# ESP32_Board.net
KiCad netlist of a schematic drawn in EasyEDA Pro
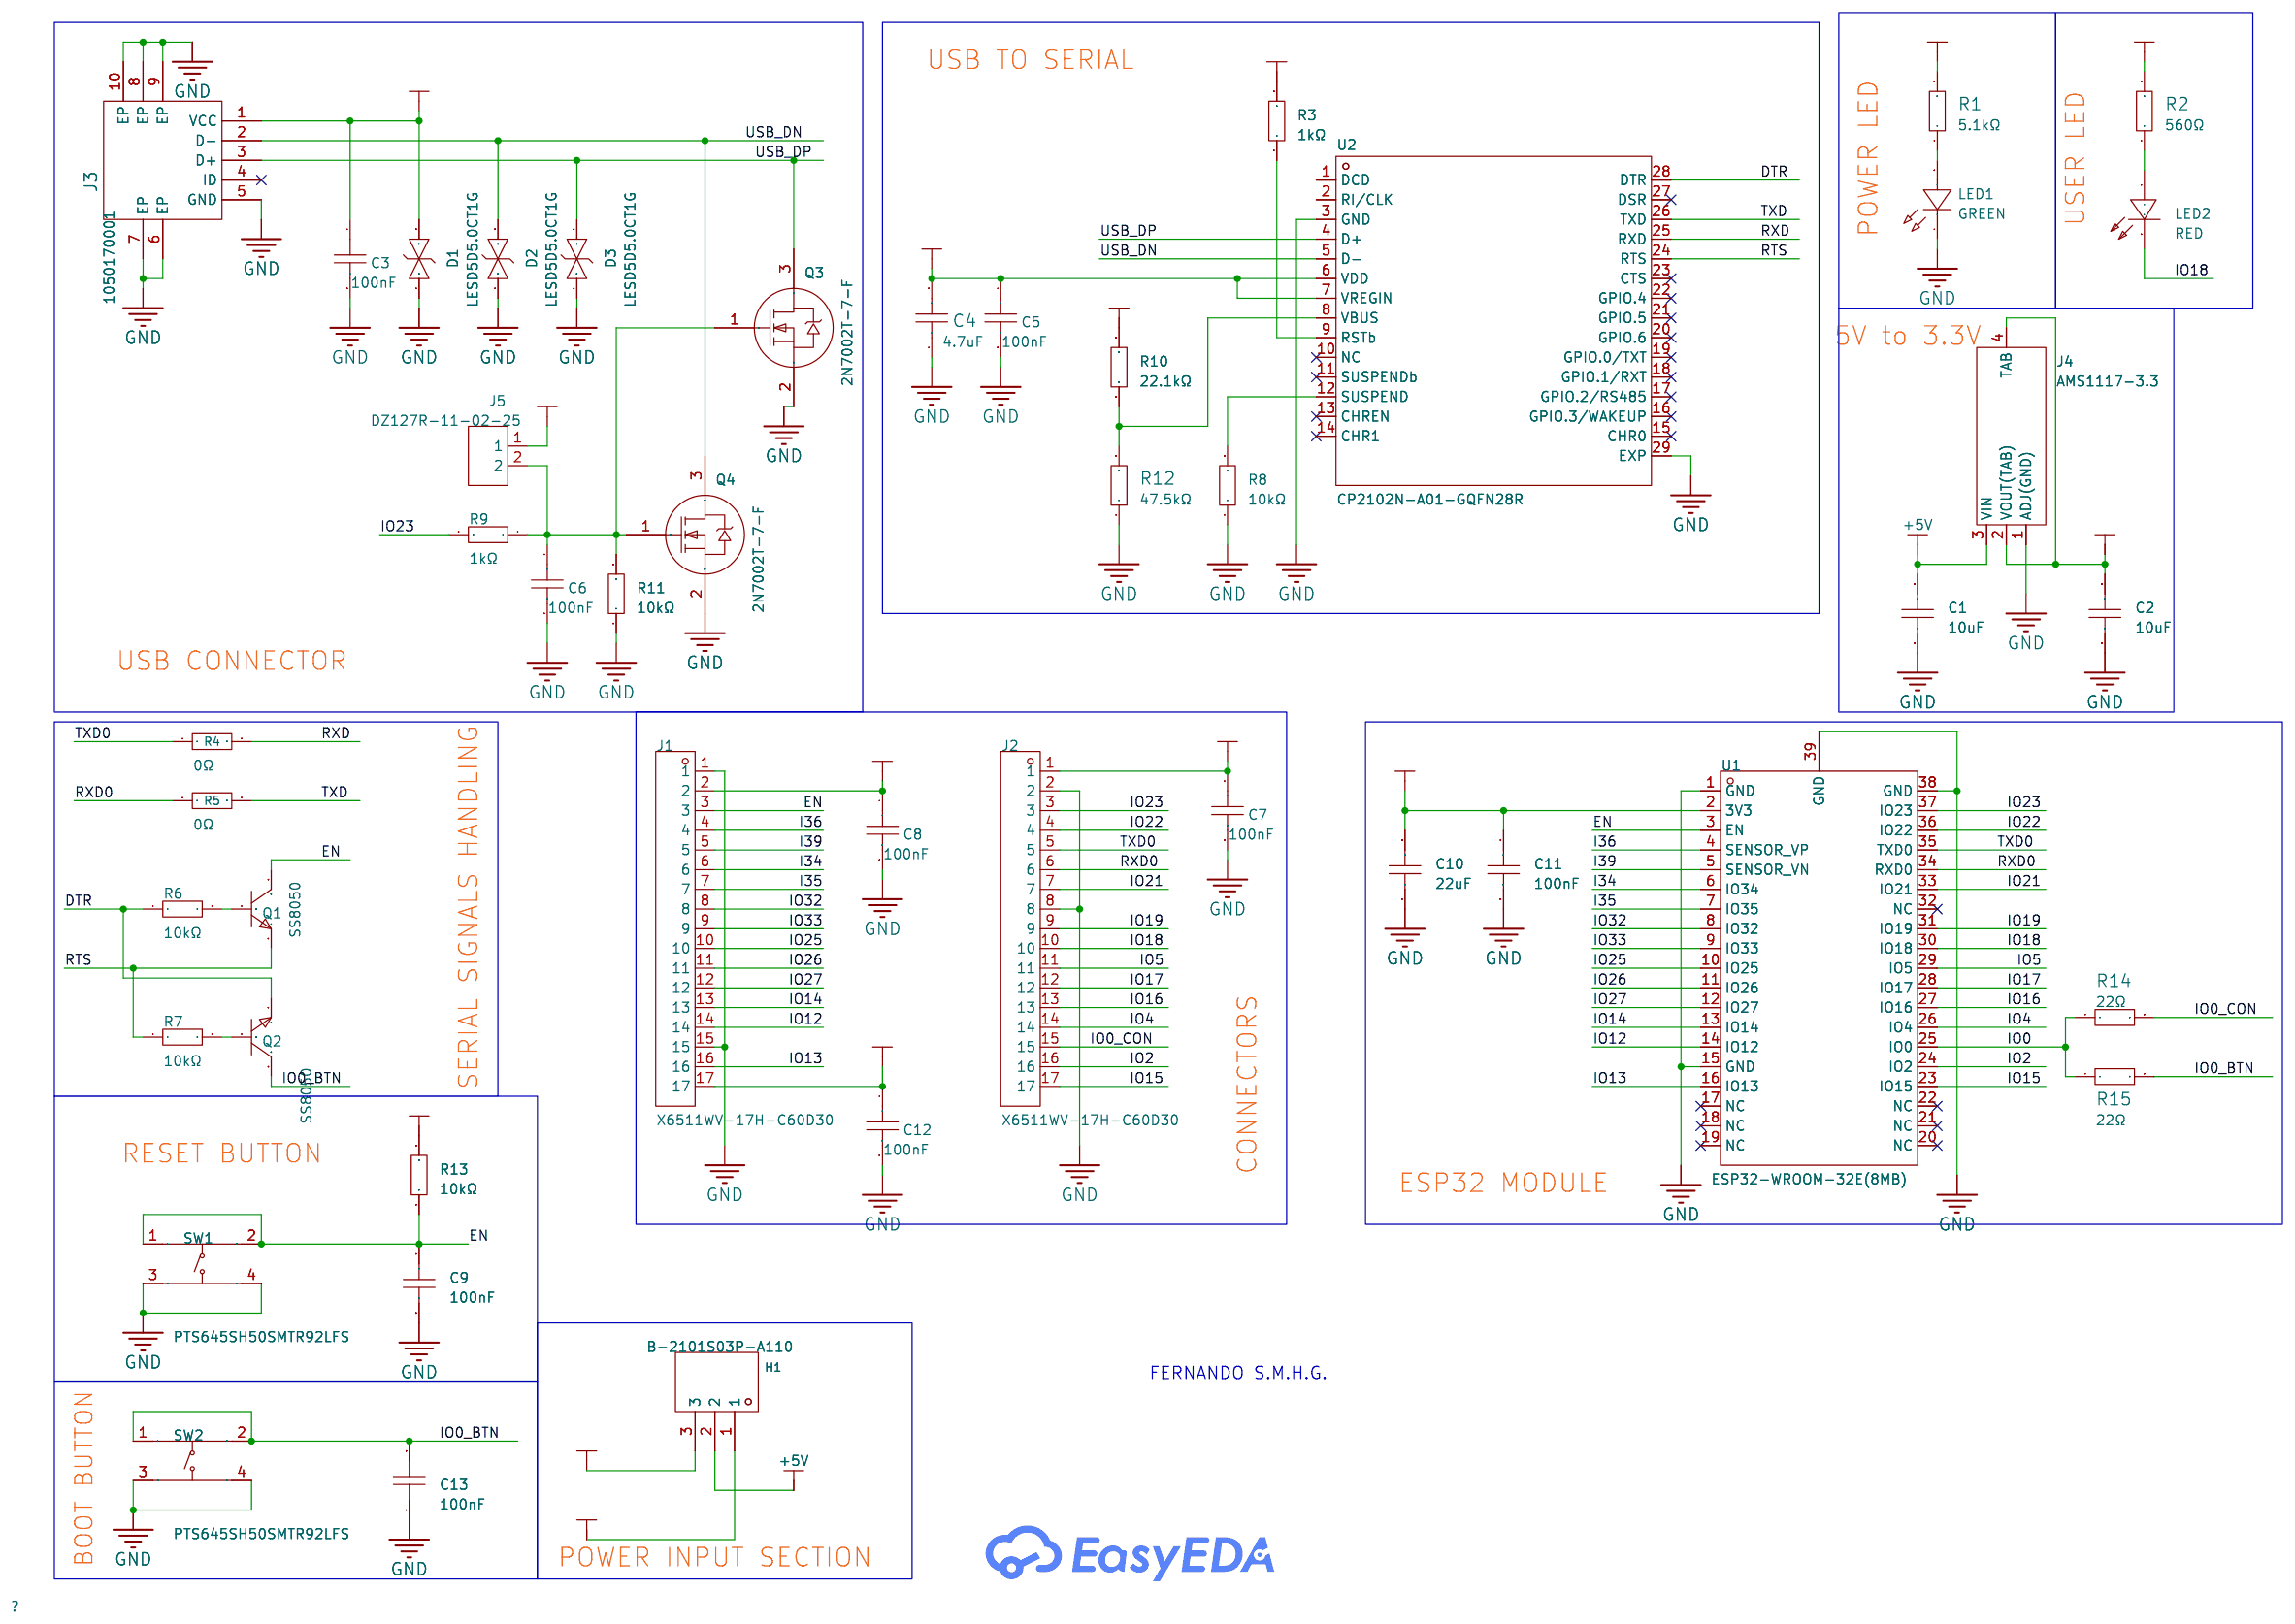
[diagram p0: schematic sheet]

(export (version "E")
  (design (tool "Eeschema 10.0.6"))
  (components
    (comp (ref "C1")
      (value "10uF")
      (footprint "easyedapro:C0402")
      (description "Capacitance:10uF Tolerance:±20% Tolerance:±20% Voltage Rating:10V Temperature Coefficient:X5R")
      (fields
        (field (name "Manufacturer Part") "CL05A106MP5NUNC")
        (field (name "Manufacturer") "SAMSUNG(三星)")
      )
      (libsource (lib "easyedapro") (part "CL05A106MP5NUNC_C315248"))
    )
    (comp (ref "C2")
      (value "10uF")
      (footprint "easyedapro:C0402")
      (description "Capacitance:10uF Tolerance:±20% Tolerance:±20% Voltage Rating:10V Temperature Coefficient:X5R")
      (fields
        (field (name "Manufacturer Part") "CL05A106MP5NUNC")
        (field (name "Manufacturer") "SAMSUNG(三星)")
      )
      (libsource (lib "easyedapro") (part "CL05A106MP5NUNC_C315248"))
    )
    (comp (ref "C3")
      (value "100nF")
      (footprint "easyedapro:C0402")
      (description "Capacitance:100nF Tolerance:±10% Tolerance:±10% Voltage Rating:16V Temperature Coefficient:X7R")
      (fields
        (field (name "Manufacturer Part") "CL05B104KO5NNNC")
        (field (name "Manufacturer") "SAMSUNG(三星)")
      )
      (libsource (lib "easyedapro") (part "CL05B104KO5NNNC"))
    )
    (comp (ref "C4")
      (value "4.7uF")
      (footprint "easyedapro:C0402")
      (description "Capacitance:4.7uF Tolerance:±10% Tolerance:±10% Voltage Rating:10V Temperature Coefficient:X5R")
      (fields
        (field (name "Manufacturer Part") "CL05A475KP5NRNC")
        (field (name "Manufacturer") "SAMSUNG(三星)")
      )
      (libsource (lib "easyedapro") (part "CL05A475KP5NRNC"))
    )
    (comp (ref "C5")
      (value "100nF")
      (footprint "easyedapro:C0402")
      (description "Capacitance:100nF Tolerance:±10% Tolerance:±10% Voltage Rating:16V Temperature Coefficient:X7R")
      (fields
        (field (name "Manufacturer Part") "CL05B104KO5NNNC")
        (field (name "Manufacturer") "SAMSUNG(三星)")
      )
      (libsource (lib "easyedapro") (part "CL05B104KO5NNNC"))
    )
    (comp (ref "C6")
      (value "100nF")
      (footprint "easyedapro:C0402")
      (description "Capacitance:100nF Tolerance:±10% Tolerance:±10% Voltage Rating:16V Temperature Coefficient:X7R")
      (fields
        (field (name "Manufacturer Part") "CL05B104KO5NNNC")
        (field (name "Manufacturer") "SAMSUNG(三星)")
      )
      (libsource (lib "easyedapro") (part "CL05B104KO5NNNC"))
    )
    (comp (ref "C7")
      (value "100nF")
      (footprint "easyedapro:C0402")
      (description "Capacitance:100nF Tolerance:±10% Tolerance:±10% Voltage Rating:16V Temperature Coefficient:X7R")
      (fields
        (field (name "Manufacturer Part") "CL05B104KO5NNNC")
        (field (name "Manufacturer") "SAMSUNG(三星)")
      )
      (libsource (lib "easyedapro") (part "CL05B104KO5NNNC"))
    )
    (comp (ref "C8")
      (value "100nF")
      (footprint "easyedapro:C0402")
      (description "Capacitance:100nF Tolerance:±10% Tolerance:±10% Voltage Rating:16V Temperature Coefficient:X7R")
      (fields
        (field (name "Manufacturer Part") "CL05B104KO5NNNC")
        (field (name "Manufacturer") "SAMSUNG(三星)")
      )
      (libsource (lib "easyedapro") (part "CL05B104KO5NNNC"))
    )
    (comp (ref "C9")
      (value "100nF")
      (footprint "easyedapro:C0402")
      (description "Capacitance:100nF Tolerance:±10% Tolerance:±10% Voltage Rating:16V Temperature Coefficient:X7R")
      (fields
        (field (name "Manufacturer Part") "CL05B104KO5NNNC")
        (field (name "Manufacturer") "SAMSUNG(三星)")
      )
      (libsource (lib "easyedapro") (part "CL05B104KO5NNNC"))
    )
    (comp (ref "C10")
      (value "22uF")
      (footprint "easyedapro:C0805")
      (description "Capacitance:22uF Tolerance:±20% Tolerance:±20% Voltage Rating:25V Temperature Coefficient:X5R")
      (fields
        (field (name "Manufacturer Part") "CL21A226MAYNNNE")
        (field (name "Manufacturer") "SAMSUNG(三星)")
      )
      (libsource (lib "easyedapro") (part "CL21A226MAYNNNE"))
    )
    (comp (ref "C11")
      (value "100nF")
      (footprint "easyedapro:C0402")
      (description "Capacitance:100nF Tolerance:±10% Tolerance:±10% Voltage Rating:16V Temperature Coefficient:X7R")
      (fields
        (field (name "Manufacturer Part") "CL05B104KO5NNNC")
        (field (name "Manufacturer") "SAMSUNG(三星)")
      )
      (libsource (lib "easyedapro") (part "CL05B104KO5NNNC"))
    )
    (comp (ref "C12")
      (value "100nF")
      (footprint "easyedapro:C0402")
      (description "Capacitance:100nF Tolerance:±10% Tolerance:±10% Voltage Rating:16V Temperature Coefficient:X7R")
      (fields
        (field (name "Manufacturer Part") "CL05B104KO5NNNC")
        (field (name "Manufacturer") "SAMSUNG(三星)")
      )
      (libsource (lib "easyedapro") (part "CL05B104KO5NNNC"))
    )
    (comp (ref "C13")
      (value "100nF")
      (footprint "easyedapro:C0402")
      (description "Capacitance:100nF Tolerance:±10% Tolerance:±10% Voltage Rating:16V Temperature Coefficient:X7R")
      (fields
        (field (name "Manufacturer Part") "CL05B104KO5NNNC")
        (field (name "Manufacturer") "SAMSUNG(三星)")
      )
      (libsource (lib "easyedapro") (part "CL05B104KO5NNNC"))
    )
    (comp (ref "D1")
      (value "LESD5D5.0CT1G")
      (footprint "easyedapro:SOD-523_L1.2-W0.8-LS1.6-BI")
      (fields (field (name "Manufacturer") "KUU"))
      (libsource (lib "easyedapro") (part "LESD5D5.0CT1G_C7433850"))
    )
    (comp (ref "D2")
      (value "LESD5D5.0CT1G")
      (footprint "easyedapro:SOD-523_L1.2-W0.8-LS1.6-BI")
      (fields (field (name "Manufacturer") "KUU"))
      (libsource (lib "easyedapro") (part "LESD5D5.0CT1G_C7433850"))
    )
    (comp (ref "D3")
      (value "LESD5D5.0CT1G")
      (footprint "easyedapro:SOD-523_L1.2-W0.8-LS1.6-BI")
      (fields (field (name "Manufacturer") "KUU"))
      (libsource (lib "easyedapro") (part "LESD5D5.0CT1G_C7433850"))
    )
    (comp (ref "H1")
      (value "B-2101S03P-A110")
      (footprint "easyedapro:HDR-TH_3P-P1.27-V-M-1")
      (fields (field (name "Manufacturer") "Ckmtw(灿科盟)"))
      (libsource (lib "easyedapro") (part "210-1S-1*3Ppin Gold-plated"))
    )
    (comp (ref "J1")
      (value "X6511WV-17H-C60D30")
      (footprint "easyedapro:HDR-TH_17P-P2.54-V-M")
      (fields (field (name "Manufacturer") "XKB Connection(中国星坤)"))
      (libsource (lib "easyedapro") (part "X6511WV-17H-C30D60"))
    )
    (comp (ref "J2")
      (value "X6511WV-17H-C60D30")
      (footprint "easyedapro:HDR-TH_17P-P2.54-V-M")
      (fields (field (name "Manufacturer") "XKB Connection(中国星坤)"))
      (libsource (lib "easyedapro") (part "X6511WV-17H-C30D60"))
    )
    (comp (ref "J3")
      (value "1050170001")
      (footprint "easyedapro:MICRO-USB-SMD_105017-0001")
      (fields (field (name "Manufacturer") "MOLEX"))
      (libsource (lib "easyedapro") (part "105017-0001"))
    )
    (comp (ref "J4")
      (value "AMS1117-3.3")
      (footprint "easyedapro:SOT-223-4_L6.5-W3.5-P2.30-LS7.0-BR")
      (fields (field (name "Manufacturer") "UMW(友台半导体)"))
      (libsource (lib "easyedapro") (part "AMS1117-3.3_C347222"))
    )
    (comp (ref "J5")
      (value "DZ127R-11-02-25")
      (footprint "easyedapro:HDR-TH_2P-P1.27-V-M")
      (fields (field (name "Manufacturer") "DEALON(德艺隆)"))
      (libsource (lib "easyedapro") (part "DZ127R-11-02-25"))
    )
    (comp (ref "LED1")
      (value "GREEN")
      (footprint "easyedapro:LED0805-RD")
      (fields (field (name "Manufacturer") "Chau Light(洲光源)"))
      (libsource (lib "easyedapro") (part "ZGH-Z2012C-10L-Z3"))
    )
    (comp (ref "LED2")
      (value "RED")
      (footprint "easyedapro:LED0805-R-RD")
      (fields (field (name "Manufacturer") "EVERLIGHT(亿光)"))
      (libsource (lib "easyedapro") (part "17-21VRD/TR8"))
    )
    (comp (ref "Q1")
      (value "SS8050")
      (footprint "easyedapro:SOT-23-3_L2.9-W1.3-P1.90-LS2.4-BR")
      (fields (field (name "Manufacturer") "CCX(晁禾)"))
      (libsource (lib "easyedapro") (part "SS8050_C51953470"))
    )
    (comp (ref "Q2")
      (value "SS8050")
      (footprint "easyedapro:SOT-23-3_L2.9-W1.3-P1.90-LS2.4-BR")
      (fields (field (name "Manufacturer") "CCX(晁禾)"))
      (libsource (lib "easyedapro") (part "SS8050_C51953470"))
    )
    (comp (ref "Q3")
      (value "2N7002T-7-F")
      (footprint "easyedapro:SOT-523-3_L1.6-W0.8-P1.00-LS1.6-BR")
      (fields (field (name "Manufacturer") "DIODES(美台)"))
      (libsource (lib "easyedapro") (part "2N7002T-7-F"))
    )
    (comp (ref "Q4")
      (value "2N7002T-7-F")
      (footprint "easyedapro:SOT-523-3_L1.6-W0.8-P1.00-LS1.6-BR")
      (fields (field (name "Manufacturer") "DIODES(美台)"))
      (libsource (lib "easyedapro") (part "2N7002T-7-F"))
    )
    (comp (ref "R1")
      (value "5.1kΩ")
      (footprint "easyedapro:R0402")
      (fields
        (field (name "Manufacturer Part") "0402WGF5101TCE")
        (field (name "Manufacturer") "UNI-ROYAL(厚声)")
      )
      (libsource (lib "easyedapro") (part "0402WGF5101TCE"))
    )
    (comp (ref "R2")
      (value "560Ω")
      (footprint "easyedapro:R0402")
      (fields
        (field (name "Manufacturer Part") "0402WGF5600TCE")
        (field (name "Manufacturer") "UNI-ROYAL(厚声)")
      )
      (libsource (lib "easyedapro") (part "0402WGF5600TCE"))
    )
    (comp (ref "R3")
      (value "1kΩ")
      (footprint "easyedapro:R0402")
      (fields
        (field (name "Manufacturer Part") "0402WGF1001TCE")
        (field (name "Manufacturer") "UNI-ROYAL(厚声)")
      )
      (libsource (lib "easyedapro") (part "0402WGF1001TCE"))
    )
    (comp (ref "R4")
      (value "0Ω")
      (footprint "easyedapro:R0402")
      (fields
        (field (name "Manufacturer Part") "0402WGF0000TCE")
        (field (name "Manufacturer") "UNI-ROYAL(厚声)")
      )
      (libsource (lib "easyedapro") (part "0402WGF0000TCE"))
    )
    (comp (ref "R5")
      (value "0Ω")
      (footprint "easyedapro:R0402")
      (fields
        (field (name "Manufacturer Part") "0402WGF0000TCE")
        (field (name "Manufacturer") "UNI-ROYAL(厚声)")
      )
      (libsource (lib "easyedapro") (part "0402WGF0000TCE"))
    )
    (comp (ref "R6")
      (value "10kΩ")
      (footprint "easyedapro:R0402")
      (fields
        (field (name "Manufacturer Part") "0402WGF1002TCE")
        (field (name "Manufacturer") "UNI-ROYAL(厚声)")
      )
      (libsource (lib "easyedapro") (part "0402WGF1002TCE"))
    )
    (comp (ref "R7")
      (value "10kΩ")
      (footprint "easyedapro:R0402")
      (fields
        (field (name "Manufacturer Part") "0402WGF1002TCE")
        (field (name "Manufacturer") "UNI-ROYAL(厚声)")
      )
      (libsource (lib "easyedapro") (part "0402WGF1002TCE"))
    )
    (comp (ref "R8")
      (value "10kΩ")
      (footprint "easyedapro:R0402")
      (fields
        (field (name "Manufacturer Part") "0402WGF1002TCE")
        (field (name "Manufacturer") "UNI-ROYAL(厚声)")
      )
      (libsource (lib "easyedapro") (part "0402WGF1002TCE"))
    )
    (comp (ref "R9")
      (value "1kΩ")
      (footprint "easyedapro:R0402")
      (fields
        (field (name "Manufacturer Part") "0402WGF1001TCE")
        (field (name "Manufacturer") "UNI-ROYAL(厚声)")
      )
      (libsource (lib "easyedapro") (part "0402WGF1001TCE"))
    )
    (comp (ref "R10")
      (value "22.1kΩ")
      (footprint "easyedapro:R0402")
      (fields
        (field (name "Manufacturer Part") "0402WGF2212TCE")
        (field (name "Manufacturer") "UNI-ROYAL(厚声)")
      )
      (libsource (lib "easyedapro") (part "0402WGF2212TCE"))
    )
    (comp (ref "R11")
      (value "10kΩ")
      (footprint "easyedapro:R0402")
      (fields
        (field (name "Manufacturer Part") "0402WGF1002TCE")
        (field (name "Manufacturer") "UNI-ROYAL(厚声)")
      )
      (libsource (lib "easyedapro") (part "0402WGF1002TCE"))
    )
    (comp (ref "R12")
      (value "47.5kΩ")
      (footprint "easyedapro:R0402")
      (fields
        (field (name "Manufacturer Part") "0402WGF4752TCE")
        (field (name "Manufacturer") "UNI-ROYAL(厚声)")
      )
      (libsource (lib "easyedapro") (part "0402WGF4752TCE"))
    )
    (comp (ref "R13")
      (value "10kΩ")
      (footprint "easyedapro:R0402")
      (fields
        (field (name "Manufacturer Part") "0402WGF1002TCE")
        (field (name "Manufacturer") "UNI-ROYAL(厚声)")
      )
      (libsource (lib "easyedapro") (part "0402WGF1002TCE"))
    )
    (comp (ref "R14")
      (value "22Ω")
      (footprint "easyedapro:R0402")
      (fields
        (field (name "Manufacturer Part") "0402WGF220JTCE")
        (field (name "Manufacturer") "UNI-ROYAL(厚声)")
      )
      (libsource (lib "easyedapro") (part "0402WGF220JTCE"))
    )
    (comp (ref "R15")
      (value "22Ω")
      (footprint "easyedapro:R0402")
      (fields
        (field (name "Manufacturer Part") "0402WGF220JTCE")
        (field (name "Manufacturer") "UNI-ROYAL(厚声)")
      )
      (libsource (lib "easyedapro") (part "0402WGF220JTCE"))
    )
    (comp (ref "SW1")
      (value "PTS645SH50SMTR92LFS")
      (footprint "easyedapro:KEY-SMD_4P-L6.0-W6.0-P4.50-LS9.0")
      (fields (field (name "Manufacturer") "C&K"))
      (libsource (lib "easyedapro") (part "PTS645SH50SMTR92LFS"))
    )
    (comp (ref "SW2")
      (value "PTS645SH50SMTR92LFS")
      (footprint "easyedapro:KEY-SMD_4P-L6.0-W6.0-P4.50-LS9.0")
      (fields (field (name "Manufacturer") "C&K"))
      (libsource (lib "easyedapro") (part "PTS645SH50SMTR92LFS"))
    )
    (comp (ref "U1")
      (value "ESP32-WROOM-32E(8MB)")
      (footprint "easyedapro:WIFI-SMD_ESP32-WROOM-32E")
      (fields
        (field (name "Manufacturer Part") "ESP32-WROOM-32E-N8")
        (field (name "Manufacturer") "ESPRESSIF(乐鑫)")
      )
      (libsource (lib "easyedapro") (part "ESP32-WROOM-32E(8MB)"))
    )
    (comp (ref "U2")
      (value "CP2102N-A01-GQFN28R")
      (footprint "easyedapro:QFN-28_L5.0-W5.0-P0.50-BL-EP3.3")
      (fields (field (name "Manufacturer") "SKYWORKS/SILICON LABS(芯科)"))
      (libsource (lib "easyedapro") (part "CP2102N-A01-GQFN28"))
    )
  )
  (nets
    (net (code "1") (name "+3V3") (class "Default")
      (node (ref "C10") (pin "2") (pinfunction "2_2") (pintype "unspecified"))
      (node (ref "C11") (pin "1") (pinfunction "1_1") (pintype "unspecified"))
      (node (ref "C2") (pin "2") (pinfunction "2_2") (pintype "unspecified"))
      (node (ref "C4") (pin "2") (pinfunction "2_2") (pintype "input"))
      (node (ref "C5") (pin "1") (pinfunction "1_1") (pintype "unspecified"))
      (node (ref "C7") (pin "1") (pinfunction "1_1") (pintype "unspecified"))
      (node (ref "C8") (pin "1") (pinfunction "1_1") (pintype "unspecified"))
      (node (ref "J1") (pin "2") (pinfunction "2_2") (pintype "unspecified"))
      (node (ref "J2") (pin "1") (pinfunction "1_1") (pintype "unspecified"))
      (node (ref "J4") (pin "2") (pinfunction "VOUT(TAB)_2") (pintype "unspecified"))
      (node (ref "J4") (pin "4") (pinfunction "TAB_4") (pintype "unspecified"))
      (node (ref "J5") (pin "1") (pinfunction "1_1") (pintype "unspecified"))
      (node (ref "R1") (pin "2") (pinfunction "2_2") (pintype "input"))
      (node (ref "R13") (pin "2") (pinfunction "2_2") (pintype "input"))
      (node (ref "R2") (pin "2") (pinfunction "2_2") (pintype "input"))
      (node (ref "R3") (pin "2") (pinfunction "2_2") (pintype "input"))
      (node (ref "U1") (pin "2") (pinfunction "3V3_2") (pintype "unspecified"))
      (node (ref "U2") (pin "6") (pinfunction "VDD_6") (pintype "unspecified"))
      (node (ref "U2") (pin "7") (pinfunction "VREGIN_7") (pintype "unspecified"))
    )
    (net (code "2") (name "+5V") (class "Default")
      (node (ref "C1") (pin "2") (pinfunction "2_2") (pintype "unspecified"))
      (node (ref "H1") (pin "2") (pinfunction "2_2") (pintype "input"))
      (node (ref "J4") (pin "3") (pinfunction "VIN_3") (pintype "unspecified"))
    )
    (net (code "3") (name "+5V_EXT") (class "Default")
      (node (ref "C12") (pin "1") (pinfunction "1_1") (pintype "unspecified"))
      (node (ref "H1") (pin "3") (pinfunction "3_3") (pintype "input"))
      (node (ref "J1") (pin "17") (pinfunction "17_17") (pintype "unspecified"))
    )
    (net (code "4") (name "+5V_VBUS") (class "Default")
      (node (ref "C3") (pin "1") (pinfunction "1_1") (pintype "unspecified"))
      (node (ref "D1") (pin "2") (pinfunction "2_2") (pintype "unspecified"))
      (node (ref "H1") (pin "1") (pinfunction "1_1") (pintype "input"))
      (node (ref "J3") (pin "1") (pinfunction "VCC_1") (pintype "input"))
      (node (ref "R10") (pin "2") (pinfunction "2_2") (pintype "input"))
    )
    (net (code "5") (name "/DTR") (class "Default")
      (node (ref "Q2") (pin "2") (pinfunction "E_2") (pintype "input"))
      (node (ref "R6") (pin "1") (pinfunction "1_1") (pintype "input"))
      (node (ref "U2") (pin "28") (pinfunction "DTR_28") (pintype "unspecified"))
    )
    (net (code "6") (name "/EN") (class "Default")
      (node (ref "C9") (pin "1") (pinfunction "1_1") (pintype "unspecified"))
      (node (ref "J1") (pin "3") (pinfunction "3_3") (pintype "unspecified"))
      (node (ref "Q1") (pin "3") (pinfunction "C_3") (pintype "input"))
      (node (ref "R13") (pin "1") (pinfunction "1_1") (pintype "input"))
      (node (ref "SW1") (pin "1") (pinfunction "1_1") (pintype "unspecified"))
      (node (ref "SW1") (pin "2") (pinfunction "2_2") (pintype "unspecified"))
      (node (ref "U1") (pin "3") (pinfunction "EN_3") (pintype "unspecified"))
    )
    (net (code "7") (name "/I34") (class "Default")
      (node (ref "J1") (pin "6") (pinfunction "6_6") (pintype "unspecified"))
      (node (ref "U1") (pin "6") (pinfunction "IO34_6") (pintype "unspecified"))
    )
    (net (code "8") (name "/I35") (class "Default")
      (node (ref "J1") (pin "7") (pinfunction "7_7") (pintype "unspecified"))
      (node (ref "U1") (pin "7") (pinfunction "IO35_7") (pintype "unspecified"))
    )
    (net (code "9") (name "/I36") (class "Default")
      (node (ref "J1") (pin "4") (pinfunction "4_4") (pintype "unspecified"))
      (node (ref "U1") (pin "4") (pinfunction "SENSOR_VP_4") (pintype "unspecified"))
    )
    (net (code "10") (name "/I39") (class "Default")
      (node (ref "J1") (pin "5") (pinfunction "5_5") (pintype "unspecified"))
      (node (ref "U1") (pin "5") (pinfunction "SENSOR_VN_5") (pintype "unspecified"))
    )
    (net (code "11") (name "/IO0") (class "Default")
      (node (ref "R14") (pin "1") (pinfunction "1_1") (pintype "input"))
      (node (ref "R15") (pin "1") (pinfunction "1_1") (pintype "input"))
      (node (ref "U1") (pin "25") (pinfunction "IO0_25") (pintype "unspecified"))
    )
    (net (code "12") (name "/IO0_BTN") (class "Default")
      (node (ref "C13") (pin "2") (pinfunction "2_2") (pintype "unspecified"))
      (node (ref "Q2") (pin "3") (pinfunction "C_3") (pintype "input"))
      (node (ref "R15") (pin "2") (pinfunction "2_2") (pintype "input"))
      (node (ref "SW2") (pin "1") (pinfunction "1_1") (pintype "unspecified"))
      (node (ref "SW2") (pin "2") (pinfunction "2_2") (pintype "unspecified"))
    )
    (net (code "13") (name "/IO0_CON") (class "Default")
      (node (ref "J2") (pin "15") (pinfunction "15_15") (pintype "unspecified"))
      (node (ref "R14") (pin "2") (pinfunction "2_2") (pintype "input"))
    )
    (net (code "14") (name "/IO2") (class "Default")
      (node (ref "J2") (pin "16") (pinfunction "16_16") (pintype "unspecified"))
      (node (ref "U1") (pin "24") (pinfunction "IO2_24") (pintype "unspecified"))
    )
    (net (code "15") (name "/IO4") (class "Default")
      (node (ref "J2") (pin "14") (pinfunction "14_14") (pintype "unspecified"))
      (node (ref "U1") (pin "26") (pinfunction "IO4_26") (pintype "unspecified"))
    )
    (net (code "16") (name "/IO5") (class "Default")
      (node (ref "J2") (pin "11") (pinfunction "11_11") (pintype "unspecified"))
      (node (ref "U1") (pin "29") (pinfunction "IO5_29") (pintype "unspecified"))
    )
    (net (code "17") (name "/IO12") (class "Default")
      (node (ref "J1") (pin "14") (pinfunction "14_14") (pintype "unspecified"))
      (node (ref "U1") (pin "14") (pinfunction "IO12_14") (pintype "unspecified"))
    )
    (net (code "18") (name "/IO13") (class "Default")
      (node (ref "J1") (pin "16") (pinfunction "16_16") (pintype "unspecified"))
      (node (ref "U1") (pin "16") (pinfunction "IO13_16") (pintype "unspecified"))
    )
    (net (code "19") (name "/IO14") (class "Default")
      (node (ref "J1") (pin "13") (pinfunction "13_13") (pintype "unspecified"))
      (node (ref "U1") (pin "13") (pinfunction "IO14_13") (pintype "unspecified"))
    )
    (net (code "20") (name "/IO15") (class "Default")
      (node (ref "J2") (pin "17") (pinfunction "17_17") (pintype "unspecified"))
      (node (ref "U1") (pin "23") (pinfunction "IO15_23") (pintype "unspecified"))
    )
    (net (code "21") (name "/IO16") (class "Default")
      (node (ref "J2") (pin "13") (pinfunction "13_13") (pintype "unspecified"))
      (node (ref "U1") (pin "27") (pinfunction "IO16_27") (pintype "unspecified"))
    )
    (net (code "22") (name "/IO17") (class "Default")
      (node (ref "J2") (pin "12") (pinfunction "12_12") (pintype "unspecified"))
      (node (ref "U1") (pin "28") (pinfunction "IO17_28") (pintype "unspecified"))
    )
    (net (code "23") (name "/IO18") (class "Default")
      (node (ref "J2") (pin "10") (pinfunction "10_10") (pintype "unspecified"))
      (node (ref "LED2") (pin "2") (pinfunction "K_2") (pintype "unspecified"))
      (node (ref "U1") (pin "30") (pinfunction "IO18_30") (pintype "unspecified"))
    )
    (net (code "24") (name "/IO19") (class "Default")
      (node (ref "J2") (pin "9") (pinfunction "9_9") (pintype "unspecified"))
      (node (ref "U1") (pin "31") (pinfunction "IO19_31") (pintype "unspecified"))
    )
    (net (code "25") (name "/IO21") (class "Default")
      (node (ref "J2") (pin "7") (pinfunction "7_7") (pintype "unspecified"))
      (node (ref "U1") (pin "33") (pinfunction "IO21_33") (pintype "unspecified"))
    )
    (net (code "26") (name "/IO22") (class "Default")
      (node (ref "J2") (pin "4") (pinfunction "4_4") (pintype "unspecified"))
      (node (ref "U1") (pin "36") (pinfunction "IO22_36") (pintype "unspecified"))
    )
    (net (code "27") (name "/IO23") (class "Default")
      (node (ref "J2") (pin "3") (pinfunction "3_3") (pintype "unspecified"))
      (node (ref "R9") (pin "2") (pinfunction "2_2") (pintype "input"))
      (node (ref "U1") (pin "37") (pinfunction "IO23_37") (pintype "unspecified"))
    )
    (net (code "28") (name "/IO25") (class "Default")
      (node (ref "J1") (pin "10") (pinfunction "10_10") (pintype "unspecified"))
      (node (ref "U1") (pin "10") (pinfunction "IO25_10") (pintype "unspecified"))
    )
    (net (code "29") (name "/IO26") (class "Default")
      (node (ref "J1") (pin "11") (pinfunction "11_11") (pintype "unspecified"))
      (node (ref "U1") (pin "11") (pinfunction "IO26_11") (pintype "unspecified"))
    )
    (net (code "30") (name "/IO27") (class "Default")
      (node (ref "J1") (pin "12") (pinfunction "12_12") (pintype "unspecified"))
      (node (ref "U1") (pin "12") (pinfunction "IO27_12") (pintype "unspecified"))
    )
    (net (code "31") (name "/IO32") (class "Default")
      (node (ref "J1") (pin "8") (pinfunction "8_8") (pintype "unspecified"))
      (node (ref "U1") (pin "8") (pinfunction "IO32_8") (pintype "unspecified"))
    )
    (net (code "32") (name "/IO33") (class "Default")
      (node (ref "J1") (pin "9") (pinfunction "9_9") (pintype "unspecified"))
      (node (ref "U1") (pin "9") (pinfunction "IO33_9") (pintype "unspecified"))
    )
    (net (code "33") (name "/RTS") (class "Default")
      (node (ref "Q1") (pin "2") (pinfunction "E_2") (pintype "input"))
      (node (ref "R7") (pin "1") (pinfunction "1_1") (pintype "input"))
      (node (ref "U2") (pin "24") (pinfunction "RTS_24") (pintype "unspecified"))
    )
    (net (code "34") (name "/RXD") (class "Default")
      (node (ref "R4") (pin "2") (pinfunction "2_2") (pintype "input"))
      (node (ref "U2") (pin "25") (pinfunction "RXD_25") (pintype "unspecified"))
    )
    (net (code "35") (name "/RXD0") (class "Default")
      (node (ref "J2") (pin "6") (pinfunction "6_6") (pintype "unspecified"))
      (node (ref "R5") (pin "1") (pinfunction "1_1") (pintype "input"))
      (node (ref "U1") (pin "34") (pinfunction "RXD0_34") (pintype "unspecified"))
    )
    (net (code "36") (name "/TXD") (class "Default")
      (node (ref "R5") (pin "2") (pinfunction "2_2") (pintype "input"))
      (node (ref "U2") (pin "26") (pinfunction "TXD_26") (pintype "unspecified"))
    )
    (net (code "37") (name "/TXD0") (class "Default")
      (node (ref "J2") (pin "5") (pinfunction "5_5") (pintype "unspecified"))
      (node (ref "R4") (pin "1") (pinfunction "1_1") (pintype "input"))
      (node (ref "U1") (pin "35") (pinfunction "TXD0_35") (pintype "unspecified"))
    )
    (net (code "38") (name "/USB_DN") (class "Default")
      (node (ref "D2") (pin "2") (pinfunction "2_2") (pintype "unspecified"))
      (node (ref "J3") (pin "2") (pinfunction "D-_2") (pintype "input"))
      (node (ref "Q4") (pin "3") (pinfunction "D_3") (pintype "unspecified"))
      (node (ref "U2") (pin "5") (pinfunction "D-_5") (pintype "unspecified"))
    )
    (net (code "39") (name "/USB_DP") (class "Default")
      (node (ref "D3") (pin "2") (pinfunction "2_2") (pintype "unspecified"))
      (node (ref "J3") (pin "3") (pinfunction "D+_3") (pintype "input"))
      (node (ref "Q3") (pin "3") (pinfunction "D_3") (pintype "unspecified"))
      (node (ref "U2") (pin "4") (pinfunction "D+_4") (pintype "unspecified"))
    )
    (net (code "40") (name "GND") (class "Default")
      (node (ref "C1") (pin "1") (pinfunction "1_1") (pintype "unspecified"))
      (node (ref "C10") (pin "1") (pinfunction "1_1") (pintype "unspecified"))
      (node (ref "C11") (pin "2") (pinfunction "2_2") (pintype "unspecified"))
      (node (ref "C12") (pin "2") (pinfunction "2_2") (pintype "unspecified"))
      (node (ref "C13") (pin "1") (pinfunction "1_1") (pintype "unspecified"))
      (node (ref "C2") (pin "1") (pinfunction "1_1") (pintype "unspecified"))
      (node (ref "C3") (pin "2") (pinfunction "2_2") (pintype "unspecified"))
      (node (ref "C4") (pin "1") (pinfunction "1_1") (pintype "input"))
      (node (ref "C5") (pin "2") (pinfunction "2_2") (pintype "unspecified"))
      (node (ref "C6") (pin "2") (pinfunction "2_2") (pintype "unspecified"))
      (node (ref "C7") (pin "2") (pinfunction "2_2") (pintype "unspecified"))
      (node (ref "C8") (pin "2") (pinfunction "2_2") (pintype "unspecified"))
      (node (ref "C9") (pin "2") (pinfunction "2_2") (pintype "unspecified"))
      (node (ref "D1") (pin "1") (pinfunction "1_1") (pintype "unspecified"))
      (node (ref "D2") (pin "1") (pinfunction "1_1") (pintype "unspecified"))
      (node (ref "D3") (pin "1") (pinfunction "1_1") (pintype "unspecified"))
      (node (ref "J1") (pin "1") (pinfunction "1_1") (pintype "unspecified"))
      (node (ref "J1") (pin "15") (pinfunction "15_15") (pintype "unspecified"))
      (node (ref "J2") (pin "2") (pinfunction "2_2") (pintype "unspecified"))
      (node (ref "J2") (pin "8") (pinfunction "8_8") (pintype "unspecified"))
      (node (ref "J3") (pin "10") (pinfunction "EP_10") (pintype "input"))
      (node (ref "J3") (pin "5") (pinfunction "GND_5") (pintype "input"))
      (node (ref "J3") (pin "6") (pinfunction "EP_6") (pintype "input"))
      (node (ref "J3") (pin "7") (pinfunction "EP_7") (pintype "input"))
      (node (ref "J3") (pin "8") (pinfunction "EP_8") (pintype "input"))
      (node (ref "J3") (pin "9") (pinfunction "EP_9") (pintype "input"))
      (node (ref "J4") (pin "1") (pinfunction "ADJ(GND)_1") (pintype "unspecified"))
      (node (ref "LED1") (pin "1") (pinfunction "K_1") (pintype "unspecified"))
      (node (ref "Q3") (pin "2") (pinfunction "S_2") (pintype "unspecified"))
      (node (ref "Q4") (pin "2") (pinfunction "S_2") (pintype "unspecified"))
      (node (ref "R11") (pin "1") (pinfunction "1_1") (pintype "input"))
      (node (ref "R12") (pin "1") (pinfunction "1_1") (pintype "input"))
      (node (ref "R8") (pin "1") (pinfunction "1_1") (pintype "input"))
      (node (ref "SW1") (pin "3") (pinfunction "3_3") (pintype "unspecified"))
      (node (ref "SW1") (pin "4") (pinfunction "4_4") (pintype "unspecified"))
      (node (ref "SW2") (pin "3") (pinfunction "3_3") (pintype "unspecified"))
      (node (ref "SW2") (pin "4") (pinfunction "4_4") (pintype "unspecified"))
      (node (ref "U1") (pin "1") (pinfunction "GND_1") (pintype "unspecified"))
      (node (ref "U1") (pin "15") (pinfunction "GND_15") (pintype "unspecified"))
      (node (ref "U1") (pin "38") (pinfunction "GND_38") (pintype "unspecified"))
      (node (ref "U1") (pin "39") (pinfunction "GND_39") (pintype "unspecified"))
      (node (ref "U2") (pin "29") (pinfunction "EXP_29") (pintype "unspecified"))
      (node (ref "U2") (pin "3") (pinfunction "GND_3") (pintype "unspecified"))
    )
    (net (code "41") (name "Net-(LED1-A)") (class "Default")
      (node (ref "LED1") (pin "2") (pinfunction "A_2") (pintype "unspecified"))
      (node (ref "R1") (pin "1") (pinfunction "1_1") (pintype "input"))
    )
    (net (code "42") (name "Net-(LED2-A)") (class "Default")
      (node (ref "LED2") (pin "1") (pinfunction "A_1") (pintype "unspecified"))
      (node (ref "R2") (pin "1") (pinfunction "1_1") (pintype "input"))
    )
    (net (code "43") (name "Net-(Q1-B)") (class "Default")
      (node (ref "Q1") (pin "1") (pinfunction "B_1") (pintype "input"))
      (node (ref "R6") (pin "2") (pinfunction "2_2") (pintype "input"))
    )
    (net (code "44") (name "Net-(Q2-B)") (class "Default")
      (node (ref "Q2") (pin "1") (pinfunction "B_1") (pintype "input"))
      (node (ref "R7") (pin "2") (pinfunction "2_2") (pintype "input"))
    )
    (net (code "45") (name "Net-(Q3-G)") (class "Default")
      (node (ref "C6") (pin "1") (pinfunction "1_1") (pintype "unspecified"))
      (node (ref "J5") (pin "2") (pinfunction "2_2") (pintype "unspecified"))
      (node (ref "Q3") (pin "1") (pinfunction "G_1") (pintype "unspecified"))
      (node (ref "Q4") (pin "1") (pinfunction "G_1") (pintype "unspecified"))
      (node (ref "R11") (pin "2") (pinfunction "2_2") (pintype "input"))
      (node (ref "R9") (pin "1") (pinfunction "1_1") (pintype "input"))
    )
    (net (code "46") (name "Net-(U2-RSTb)") (class "Default")
      (node (ref "R3") (pin "1") (pinfunction "1_1") (pintype "input"))
      (node (ref "U2") (pin "9") (pinfunction "RSTb_9") (pintype "unspecified"))
    )
    (net (code "47") (name "Net-(U2-SUSPEND)") (class "Default")
      (node (ref "R8") (pin "2") (pinfunction "2_2") (pintype "input"))
      (node (ref "U2") (pin "12") (pinfunction "SUSPEND_12") (pintype "unspecified"))
    )
    (net (code "48") (name "Net-(U2-VBUS)") (class "Default")
      (node (ref "R10") (pin "1") (pinfunction "1_1") (pintype "input"))
      (node (ref "R12") (pin "2") (pinfunction "2_2") (pintype "input"))
      (node (ref "U2") (pin "8") (pinfunction "VBUS_8") (pintype "unspecified"))
    )
    (net (code "49") (name "unconnected-(J3-ID-Pad4)") (class "Default")
      (node (ref "J3") (pin "4") (pinfunction "ID_4") (pintype "input+no_connect"))
    )
    (net (code "50") (name "unconnected-(U1-NC-Pad17)") (class "Default")
      (node (ref "U1") (pin "17") (pinfunction "NC_17") (pintype "unspecified+no_connect"))
    )
    (net (code "51") (name "unconnected-(U1-NC-Pad18)") (class "Default")
      (node (ref "U1") (pin "18") (pinfunction "NC_18") (pintype "unspecified+no_connect"))
    )
    (net (code "52") (name "unconnected-(U1-NC-Pad19)") (class "Default")
      (node (ref "U1") (pin "19") (pinfunction "NC_19") (pintype "unspecified+no_connect"))
    )
    (net (code "53") (name "unconnected-(U1-NC-Pad20)") (class "Default")
      (node (ref "U1") (pin "20") (pinfunction "NC_20") (pintype "unspecified+no_connect"))
    )
    (net (code "54") (name "unconnected-(U1-NC-Pad21)") (class "Default")
      (node (ref "U1") (pin "21") (pinfunction "NC_21") (pintype "unspecified+no_connect"))
    )
    (net (code "55") (name "unconnected-(U1-NC-Pad22)") (class "Default")
      (node (ref "U1") (pin "22") (pinfunction "NC_22") (pintype "unspecified+no_connect"))
    )
    (net (code "56") (name "unconnected-(U1-NC-Pad32)") (class "Default")
      (node (ref "U1") (pin "32") (pinfunction "NC_32") (pintype "unspecified+no_connect"))
    )
    (net (code "57") (name "unconnected-(U2-CHR0-Pad15)") (class "Default")
      (node (ref "U2") (pin "15") (pinfunction "CHR0_15") (pintype "unspecified+no_connect"))
    )
    (net (code "58") (name "unconnected-(U2-CHR1-Pad14)") (class "Default")
      (node (ref "U2") (pin "14") (pinfunction "CHR1_14") (pintype "unspecified+no_connect"))
    )
    (net (code "59") (name "unconnected-(U2-CHREN-Pad13)") (class "Default")
      (node (ref "U2") (pin "13") (pinfunction "CHREN_13") (pintype "unspecified+no_connect"))
    )
    (net (code "60") (name "unconnected-(U2-CTS-Pad23)") (class "Default")
      (node (ref "U2") (pin "23") (pinfunction "CTS_23") (pintype "unspecified+no_connect"))
    )
    (net (code "61") (name "unconnected-(U2-DCD-Pad1)") (class "Default")
      (node (ref "U2") (pin "1") (pinfunction "DCD_1") (pintype "unspecified"))
    )
    (net (code "62") (name "unconnected-(U2-DSR-Pad27)") (class "Default")
      (node (ref "U2") (pin "27") (pinfunction "DSR_27") (pintype "unspecified+no_connect"))
    )
    (net (code "63") (name "unconnected-(U2-GPIO.0{slash}TXT-Pad19)") (class "Default")
      (node (ref "U2") (pin "19") (pinfunction "GPIO.0/TXT_19") (pintype "unspecified+no_connect"))
    )
    (net (code "64") (name "unconnected-(U2-GPIO.1{slash}RXT-Pad18)") (class "Default")
      (node (ref "U2") (pin "18") (pinfunction "GPIO.1/RXT_18") (pintype "unspecified+no_connect"))
    )
    (net (code "65") (name "unconnected-(U2-GPIO.2{slash}RS485-Pad17)") (class "Default")
      (node (ref "U2") (pin "17") (pinfunction "GPIO.2/RS485_17") (pintype "unspecified+no_connect"))
    )
    (net (code "66") (name "unconnected-(U2-GPIO.3{slash}WAKEUP-Pad16)") (class "Default")
      (node (ref "U2") (pin "16") (pinfunction "GPIO.3/WAKEUP_16") (pintype "unspecified+no_connect"))
    )
    (net (code "67") (name "unconnected-(U2-GPIO.4-Pad22)") (class "Default")
      (node (ref "U2") (pin "22") (pinfunction "GPIO.4_22") (pintype "unspecified+no_connect"))
    )
    (net (code "68") (name "unconnected-(U2-GPIO.5-Pad21)") (class "Default")
      (node (ref "U2") (pin "21") (pinfunction "GPIO.5_21") (pintype "unspecified+no_connect"))
    )
    (net (code "69") (name "unconnected-(U2-GPIO.6-Pad20)") (class "Default")
      (node (ref "U2") (pin "20") (pinfunction "GPIO.6_20") (pintype "unspecified+no_connect"))
    )
    (net (code "70") (name "unconnected-(U2-NC-Pad10)") (class "Default")
      (node (ref "U2") (pin "10") (pinfunction "NC_10") (pintype "unspecified+no_connect"))
    )
    (net (code "71") (name "unconnected-(U2-RI{slash}CLK-Pad2)") (class "Default")
      (node (ref "U2") (pin "2") (pinfunction "RI/CLK_2") (pintype "unspecified"))
    )
    (net (code "72") (name "unconnected-(U2-SUSPENDb-Pad11)") (class "Default")
      (node (ref "U2") (pin "11") (pinfunction "SUSPENDb_11") (pintype "unspecified+no_connect"))
    )
  )
)
